# bpod_stepper_1_2_3.net
KiCad netlist of a schematic drawn in EAGLE
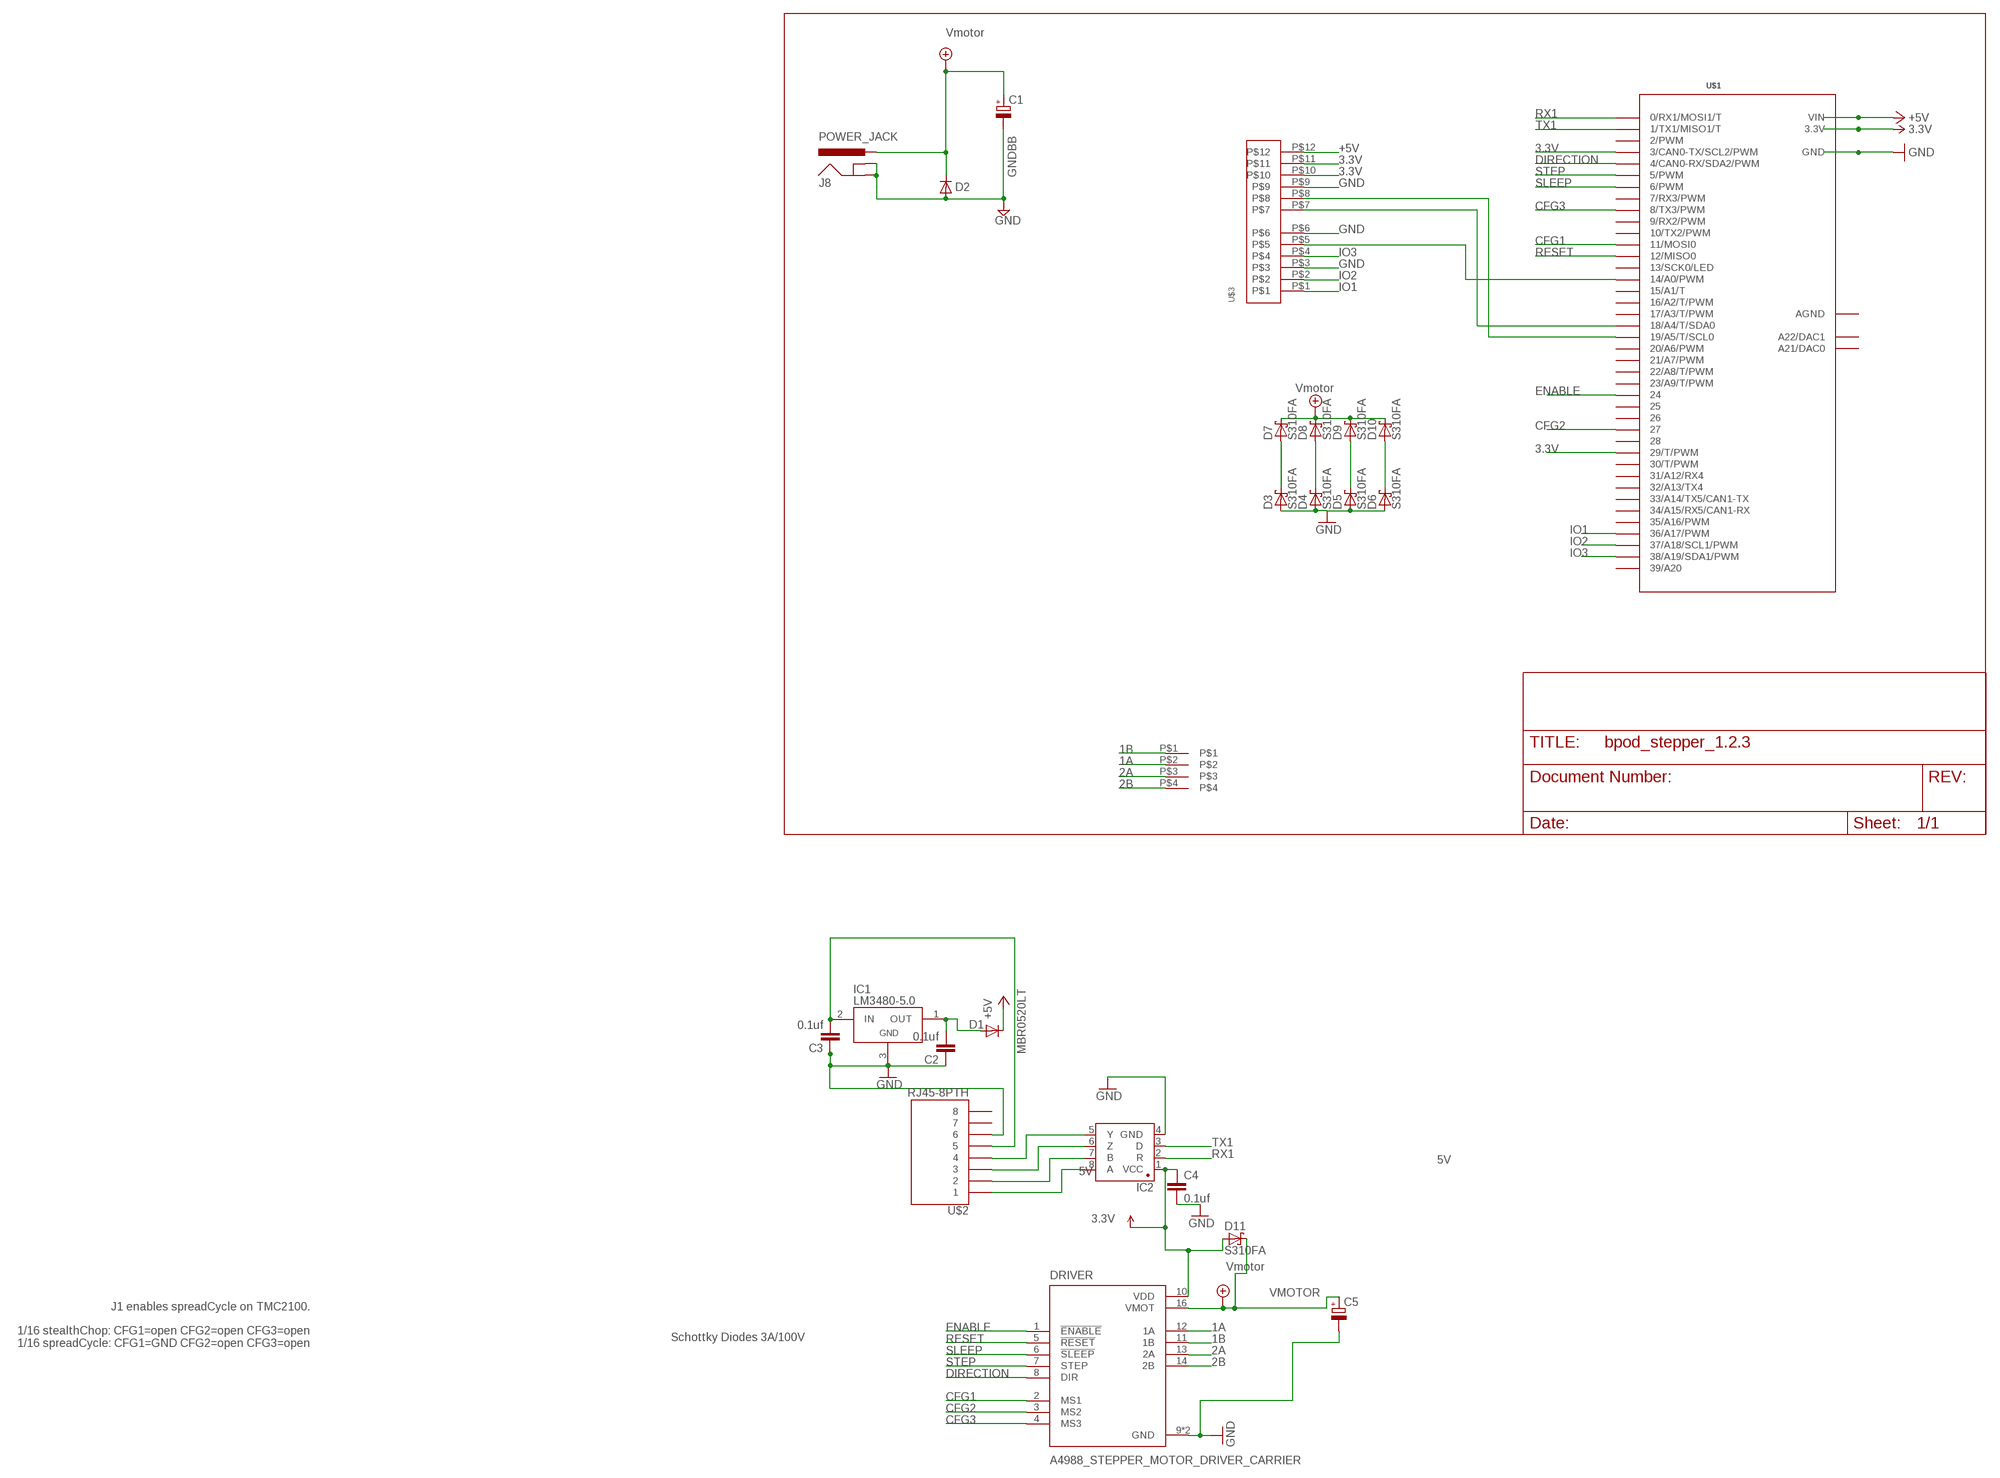
[diagram p0: schematic, sheet 1]

(export (version "E")
  (design (tool "Eeschema 10.0.6"))
  (components
    (comp (ref "C1")
      (value "CPOL-EUG")
      (footprint "eagle-import:PANASONIC_G")
      (libsource (lib "eagle-import") (part "CPOL-EUG"))
    )
    (comp (ref "C2")
      (value "0.1uf")
      (footprint "eagle-import:1206@1")
      (libsource (lib "eagle-import") (part "CAP1206"))
    )
    (comp (ref "C3")
      (value "0.1uf")
      (footprint "eagle-import:1206@1")
      (libsource (lib "eagle-import") (part "CAP1206"))
    )
    (comp (ref "C4")
      (value "0.1uf")
      (footprint "eagle-import:1206@1")
      (libsource (lib "eagle-import") (part "CAP1206"))
    )
    (comp (ref "C5")
      (value "CPOL-EUG")
      (footprint "eagle-import:PANASONIC_G")
      (libsource (lib "eagle-import") (part "CPOL-EUG"))
    )
    (comp (ref "D1")
      (value "MBR0520LT")
      (footprint "eagle-import:SOD123")
      (libsource (lib "eagle-import") (part "MBR0520LT"))
    )
    (comp (ref "D2")
      (value "DIODE-DO214AA")
      (footprint "eagle-import:DO214AA")
      (libsource (lib "eagle-import") (part "DIODE-DO214AA"))
    )
    (comp (ref "D3")
      (value "S310FA")
      (footprint "eagle-import:SOD123")
      (libsource (lib "eagle-import") (part "D_SCHOTTKY-SOD123"))
    )
    (comp (ref "D4")
      (value "S310FA")
      (footprint "eagle-import:SOD123")
      (libsource (lib "eagle-import") (part "D_SCHOTTKY-SOD123"))
    )
    (comp (ref "D5")
      (value "S310FA")
      (footprint "eagle-import:SOD123")
      (libsource (lib "eagle-import") (part "D_SCHOTTKY-SOD123"))
    )
    (comp (ref "D6")
      (value "S310FA")
      (footprint "eagle-import:SOD123")
      (libsource (lib "eagle-import") (part "D_SCHOTTKY-SOD123"))
    )
    (comp (ref "D7")
      (value "S310FA")
      (footprint "eagle-import:SOD123")
      (libsource (lib "eagle-import") (part "D_SCHOTTKY-SOD123"))
    )
    (comp (ref "D8")
      (value "S310FA")
      (footprint "eagle-import:SOD123")
      (libsource (lib "eagle-import") (part "D_SCHOTTKY-SOD123"))
    )
    (comp (ref "D9")
      (value "S310FA")
      (footprint "eagle-import:SOD123")
      (libsource (lib "eagle-import") (part "D_SCHOTTKY-SOD123"))
    )
    (comp (ref "D10")
      (value "S310FA")
      (footprint "eagle-import:SOD123")
      (libsource (lib "eagle-import") (part "D_SCHOTTKY-SOD123"))
    )
    (comp (ref "D11")
      (value "S310FA")
      (footprint "eagle-import:SOD123")
      (libsource (lib "eagle-import") (part "D_SCHOTTKY-SOD123"))
    )
    (comp (ref "DRIVER")
      (value "A4988_STEPPER_MOTOR_DRIVER_CARRIER")
      (footprint "eagle-import:MODULE_A4988_STEPPER_MOTOR_DRIVER_CARRIER")
      (fields (field (name "MF") "Pololu") (field (name "MP") "A4988 STEPPER MOTOR DRIVER CARRIER"))
      (libsource (lib "eagle-import") (part "A4988_STEPPER_MOTOR_DRIVER_CARRIER"))
    )
    (comp (ref "IC1")
      (value "LM3480-5.0")
      (footprint "eagle-import:SOT-23-3")
      (libsource (lib "eagle-import") (part "LM3480-5.0"))
    )
    (comp (ref "IC2")
      (value "SN65HVD31DR")
      (footprint "eagle-import:SO08")
      (libsource (lib "eagle-import") (part "SN65HVD31DR"))
    )
    (comp (ref "J8")
      (value "POWER_JACK")
      (footprint "eagle-import:POWER_JACK_PTH")
      (libsource (lib "eagle-import") (part "POWER_JACK"))
    )
    (comp (ref "U$1")
      (value "TEENSY_3.6_DIL")
      (footprint "eagle-import:TEENSY_3.6_DIL")
      (libsource (lib "eagle-import") (part "TEENSY_3.6_DIL"))
    )
    (comp (ref "U$2")
      (value "RJ45-8PTH")
      (footprint "eagle-import:RJ45-8")
      (libsource (lib "eagle-import") (part "RJ45-8PTH"))
    )
    (comp (ref "U$3")
      (value "12POS_MOLEX_SOCKET")
      (footprint "eagle-import:12POS_MOLEX_SOCKET")
      (libsource (lib "eagle-import") (part "12POS_MOLEX_SOCKET"))
    )
    (comp (ref "U$4")
      (value "MOLEX395221004")
      (footprint "eagle-import:MOLEX395221004")
      (libsource (lib "eagle-import") (part "MOLEX395221004"))
    )
  )
  (nets
    (net (code "1") (name "+5V") (class "Default")
      (node (ref "D1") (pin "C") (pinfunction "C_C") (pintype "passive"))
      (node (ref "U$1") (pin "VIN") (pinfunction "VIN_VIN") (pintype "power_in"))
      (node (ref "U$3") (pin "P$12") (pinfunction "P$12_P$12") (pintype "bidirectional"))
    )
    (net (code "2") (name "/1A") (class "Default")
      (node (ref "D4") (pin "C") (pinfunction "C_C") (pintype "passive"))
      (node (ref "D8") (pin "A") (pinfunction "A_A") (pintype "passive"))
      (node (ref "DRIVER") (pin "12") (pinfunction "1A_12") (pintype "output"))
      (node (ref "U$4") (pin "P$2") (pinfunction "P$2_P$2") (pintype "bidirectional"))
    )
    (net (code "3") (name "/1B") (class "Default")
      (node (ref "D3") (pin "C") (pinfunction "C_C") (pintype "passive"))
      (node (ref "D7") (pin "A") (pinfunction "A_A") (pintype "passive"))
      (node (ref "DRIVER") (pin "11") (pinfunction "1B_11") (pintype "output"))
      (node (ref "U$4") (pin "P$1") (pinfunction "P$1_P$1") (pintype "bidirectional"))
    )
    (net (code "4") (name "/2A") (class "Default")
      (node (ref "D5") (pin "C") (pinfunction "C_C") (pintype "passive"))
      (node (ref "D9") (pin "A") (pinfunction "A_A") (pintype "passive"))
      (node (ref "DRIVER") (pin "13") (pinfunction "2A_13") (pintype "output"))
      (node (ref "U$4") (pin "P$3") (pinfunction "P$3_P$3") (pintype "bidirectional"))
    )
    (net (code "5") (name "/2B") (class "Default")
      (node (ref "D10") (pin "A") (pinfunction "A_A") (pintype "passive"))
      (node (ref "D6") (pin "C") (pinfunction "C_C") (pintype "passive"))
      (node (ref "DRIVER") (pin "14") (pinfunction "2B_14") (pintype "output"))
      (node (ref "U$4") (pin "P$4") (pinfunction "P$4_P$4") (pintype "bidirectional"))
    )
    (net (code "6") (name "/AGND") (class "Default")
      (node (ref "U$1") (pin "AGND") (pinfunction "AGND_AGND") (pintype "power_in"))
    )
    (net (code "7") (name "/CFG1") (class "Default")
      (node (ref "DRIVER") (pin "2") (pinfunction "MS1_2") (pintype "input"))
      (node (ref "U$1") (pin "11") (pinfunction "11/MOSI0_11") (pintype "bidirectional"))
    )
    (net (code "8") (name "/CFG2") (class "Default")
      (node (ref "DRIVER") (pin "3") (pinfunction "MS2_3") (pintype "input"))
      (node (ref "U$1") (pin "27") (pinfunction "27_27") (pintype "bidirectional"))
    )
    (net (code "9") (name "/CFG3") (class "Default")
      (node (ref "DRIVER") (pin "4") (pinfunction "MS3_4") (pintype "input"))
      (node (ref "U$1") (pin "8") (pinfunction "8/TX3/PWM_8") (pintype "bidirectional"))
    )
    (net (code "10") (name "/DIRECTION") (class "Default")
      (node (ref "DRIVER") (pin "8") (pinfunction "DIR_8") (pintype "input"))
      (node (ref "U$1") (pin "4") (pinfunction "4/CAN0-RX/SDA2/PWM_4") (pintype "bidirectional"))
    )
    (net (code "11") (name "/ENABLE") (class "Default")
      (node (ref "DRIVER") (pin "1") (pinfunction "~{ENABLE}_1") (pintype "input"))
      (node (ref "U$1") (pin "24") (pinfunction "24_24") (pintype "bidirectional"))
    )
    (net (code "12") (name "/IO1") (class "Default")
      (node (ref "U$1") (pin "36/A17") (pinfunction "36/A17/PWM_36/A17") (pintype "bidirectional"))
      (node (ref "U$3") (pin "P$1") (pinfunction "P$1_P$1") (pintype "bidirectional"))
    )
    (net (code "13") (name "/IO2") (class "Default")
      (node (ref "U$1") (pin "37/A18") (pinfunction "37/A18/SCL1/PWM_37/A18") (pintype "bidirectional"))
      (node (ref "U$3") (pin "P$2") (pinfunction "P$2_P$2") (pintype "bidirectional"))
    )
    (net (code "14") (name "/IO3") (class "Default")
      (node (ref "U$1") (pin "38/A19") (pinfunction "38/A19/SDA1/PWM_38/A19") (pintype "bidirectional"))
      (node (ref "U$3") (pin "P$4") (pinfunction "P$4_P$4") (pintype "bidirectional"))
    )
    (net (code "15") (name "/RESET") (class "Default")
      (node (ref "DRIVER") (pin "5") (pinfunction "~{RESET}_5") (pintype "input"))
      (node (ref "U$1") (pin "12") (pinfunction "12/MISO0_12") (pintype "bidirectional"))
    )
    (net (code "16") (name "/RX1") (class "Default")
      (node (ref "IC2") (pin "2") (pinfunction "R_2") (pintype "bidirectional"))
      (node (ref "U$1") (pin "0") (pinfunction "0/RX1/MOSI1/T_0") (pintype "bidirectional"))
    )
    (net (code "17") (name "/SLEEP") (class "Default")
      (node (ref "DRIVER") (pin "6") (pinfunction "~{SLEEP}_6") (pintype "input"))
      (node (ref "U$1") (pin "6") (pinfunction "6/PWM_6") (pintype "bidirectional"))
    )
    (net (code "18") (name "/STEP") (class "Default")
      (node (ref "DRIVER") (pin "7") (pinfunction "STEP_7") (pintype "input"))
      (node (ref "U$1") (pin "5") (pinfunction "5/PWM_5") (pintype "bidirectional"))
    )
    (net (code "19") (name "/TX1") (class "Default")
      (node (ref "IC2") (pin "3") (pinfunction "D_3") (pintype "bidirectional"))
      (node (ref "U$1") (pin "1") (pinfunction "1/TX1/MISO1/T_1") (pintype "bidirectional"))
    )
    (net (code "20") (name "3.3V") (class "Default")
      (node (ref "C4") (pin "1") (pinfunction "1_1") (pintype "passive"))
      (node (ref "D11") (pin "A") (pinfunction "A_A") (pintype "passive"))
      (node (ref "DRIVER") (pin "10") (pinfunction "VDD_10") (pintype "power_in"))
      (node (ref "IC2") (pin "1") (pinfunction "VCC_1") (pintype "bidirectional"))
      (node (ref "U$1") (pin "29") (pinfunction "29/T/PWM_29") (pintype "bidirectional"))
      (node (ref "U$1") (pin "3") (pinfunction "3/CAN0-TX/SCL2/PWM_3") (pintype "bidirectional"))
      (node (ref "U$1") (pin "3.3V") (pinfunction "3.3V_3.3V") (pintype "power_in"))
      (node (ref "U$1") (pin "3.3V3") (pinfunction "3.3V_3.3V3") (pintype "power_in"))
      (node (ref "U$3") (pin "P$10") (pinfunction "P$10_P$10") (pintype "bidirectional"))
      (node (ref "U$3") (pin "P$11") (pinfunction "P$11_P$11") (pintype "bidirectional"))
    )
    (net (code "21") (name "GND") (class "Default")
      (node (ref "C1") (pin "-") (pinfunction "-_-") (pintype "passive"))
      (node (ref "C2") (pin "1") (pinfunction "1_1") (pintype "passive"))
      (node (ref "C3") (pin "1") (pinfunction "1_1") (pintype "passive"))
      (node (ref "C4") (pin "2") (pinfunction "2_2") (pintype "passive"))
      (node (ref "C5") (pin "-") (pinfunction "-_-") (pintype "passive"))
      (node (ref "D2") (pin "A") (pinfunction "A_A") (pintype "passive"))
      (node (ref "D3") (pin "A") (pinfunction "A_A") (pintype "passive"))
      (node (ref "D4") (pin "A") (pinfunction "A_A") (pintype "passive"))
      (node (ref "D5") (pin "A") (pinfunction "A_A") (pintype "passive"))
      (node (ref "D6") (pin "A") (pinfunction "A_A") (pintype "passive"))
      (node (ref "DRIVER") (pin "15") (pinfunction "GND_15") (pintype "power_in"))
      (node (ref "DRIVER") (pin "9") (pinfunction "GND_9") (pintype "power_in"))
      (node (ref "IC1") (pin "3") (pinfunction "GND_3") (pintype "power_in"))
      (node (ref "IC2") (pin "4") (pinfunction "GND_4") (pintype "bidirectional"))
      (node (ref "J8") (pin "GND") (pinfunction "GND_GND") (pintype "bidirectional"))
      (node (ref "J8") (pin "GNDBREAK") (pinfunction "GNDBREAK_GNDBREAK") (pintype "bidirectional"))
      (node (ref "U$1") (pin "GND") (pinfunction "GND_GND") (pintype "power_in"))
      (node (ref "U$1") (pin "GND1") (pinfunction "GND_GND1") (pintype "power_in"))
      (node (ref "U$2") (pin "6") (pinfunction "6_6") (pintype "bidirectional"))
      (node (ref "U$3") (pin "P$3") (pinfunction "P$3_P$3") (pintype "bidirectional"))
      (node (ref "U$3") (pin "P$6") (pinfunction "P$6_P$6") (pintype "bidirectional"))
      (node (ref "U$3") (pin "P$9") (pinfunction "P$9_P$9") (pintype "bidirectional"))
    )
    (net (code "22") (name "Net-(IC1-IN)") (class "Default")
      (node (ref "C3") (pin "2") (pinfunction "2_2") (pintype "passive"))
      (node (ref "IC1") (pin "2") (pinfunction "IN_2") (pintype "power_in"))
      (node (ref "U$2") (pin "5") (pinfunction "5_5") (pintype "bidirectional"))
    )
    (net (code "23") (name "Net-(IC1-OUT)") (class "Default")
      (node (ref "C2") (pin "2") (pinfunction "2_2") (pintype "passive"))
      (node (ref "D1") (pin "A") (pinfunction "A_A") (pintype "passive"))
      (node (ref "IC1") (pin "1") (pinfunction "OUT_1") (pintype "power_in"))
    )
    (net (code "24") (name "Net-(IC2-A)") (class "Default")
      (node (ref "IC2") (pin "8") (pinfunction "A_8") (pintype "bidirectional"))
      (node (ref "U$2") (pin "1") (pinfunction "1_1") (pintype "bidirectional"))
    )
    (net (code "25") (name "Net-(IC2-B)") (class "Default")
      (node (ref "IC2") (pin "7") (pinfunction "B_7") (pintype "bidirectional"))
      (node (ref "U$2") (pin "2") (pinfunction "2_2") (pintype "bidirectional"))
    )
    (net (code "26") (name "Net-(IC2-Y)") (class "Default")
      (node (ref "IC2") (pin "5") (pinfunction "Y_5") (pintype "bidirectional"))
      (node (ref "U$2") (pin "4") (pinfunction "4_4") (pintype "bidirectional"))
    )
    (net (code "27") (name "Net-(IC2-Z)") (class "Default")
      (node (ref "IC2") (pin "6") (pinfunction "Z_6") (pintype "bidirectional"))
      (node (ref "U$2") (pin "3") (pinfunction "3_3") (pintype "bidirectional"))
    )
    (net (code "28") (name "Net-(U$1-14{slash}A0{slash}PWM)") (class "Default")
      (node (ref "U$1") (pin "14/A0") (pinfunction "14/A0/PWM_14/A0") (pintype "bidirectional"))
      (node (ref "U$3") (pin "P$5") (pinfunction "P$5_P$5") (pintype "bidirectional"))
    )
    (net (code "29") (name "Net-(U$1-18{slash}A4{slash}T{slash}SDA0)") (class "Default")
      (node (ref "U$1") (pin "18/A4") (pinfunction "18/A4/T/SDA0_18/A4") (pintype "bidirectional"))
      (node (ref "U$3") (pin "P$7") (pinfunction "P$7_P$7") (pintype "bidirectional"))
    )
    (net (code "30") (name "Net-(U$1-19{slash}A5{slash}T{slash}SCL0)") (class "Default")
      (node (ref "U$1") (pin "19/A5") (pinfunction "19/A5/T/SCL0_19/A5") (pintype "bidirectional"))
      (node (ref "U$3") (pin "P$8") (pinfunction "P$8_P$8") (pintype "bidirectional"))
    )
    (net (code "31") (name "Vmotor") (class "Default")
      (node (ref "C1") (pin "+") (pinfunction "+_+") (pintype "passive"))
      (node (ref "C5") (pin "+") (pinfunction "+_+") (pintype "passive"))
      (node (ref "D10") (pin "C") (pinfunction "C_C") (pintype "passive"))
      (node (ref "D11") (pin "C") (pinfunction "C_C") (pintype "passive"))
      (node (ref "D2") (pin "C") (pinfunction "C_C") (pintype "passive"))
      (node (ref "D7") (pin "C") (pinfunction "C_C") (pintype "passive"))
      (node (ref "D8") (pin "C") (pinfunction "C_C") (pintype "passive"))
      (node (ref "D9") (pin "C") (pinfunction "C_C") (pintype "passive"))
      (node (ref "DRIVER") (pin "16") (pinfunction "VMOT_16") (pintype "power_in"))
      (node (ref "J8") (pin "PWR") (pinfunction "PWR_PWR") (pintype "bidirectional"))
    )
    (net (code "32") (name "unconnected-(U$1-2{slash}PWM-Pad2)") (class "Default")
      (node (ref "U$1") (pin "2") (pinfunction "2/PWM_2") (pintype "bidirectional"))
    )
    (net (code "33") (name "unconnected-(U$1-7{slash}RX3{slash}PWM-Pad7)") (class "Default")
      (node (ref "U$1") (pin "7") (pinfunction "7/RX3/PWM_7") (pintype "bidirectional"))
    )
    (net (code "34") (name "unconnected-(U$1-9{slash}RX2{slash}PWM-Pad9)") (class "Default")
      (node (ref "U$1") (pin "9") (pinfunction "9/RX2/PWM_9") (pintype "bidirectional"))
    )
    (net (code "35") (name "unconnected-(U$1-10{slash}TX2{slash}PWM-Pad10)") (class "Default")
      (node (ref "U$1") (pin "10") (pinfunction "10/TX2/PWM_10") (pintype "bidirectional"))
    )
    (net (code "36") (name "unconnected-(U$1-13{slash}SCK0{slash}LED-Pad13)") (class "Default")
      (node (ref "U$1") (pin "13") (pinfunction "13/SCK0/LED_13") (pintype "bidirectional"))
    )
    (net (code "37") (name "unconnected-(U$1-15{slash}A1{slash}T-Pad15{slash}A1)") (class "Default")
      (node (ref "U$1") (pin "15/A1") (pinfunction "15/A1/T_15/A1") (pintype "bidirectional"))
    )
    (net (code "38") (name "unconnected-(U$1-16{slash}A2{slash}T{slash}PWM-Pad16{slash}A2)") (class "Default")
      (node (ref "U$1") (pin "16/A2") (pinfunction "16/A2/T/PWM_16/A2") (pintype "bidirectional"))
    )
    (net (code "39") (name "unconnected-(U$1-17{slash}A3{slash}T{slash}PWM-Pad17{slash}A3)") (class "Default")
      (node (ref "U$1") (pin "17/A3") (pinfunction "17/A3/T/PWM_17/A3") (pintype "bidirectional"))
    )
    (net (code "40") (name "unconnected-(U$1-20{slash}A6{slash}PWM-Pad20{slash}A6)") (class "Default")
      (node (ref "U$1") (pin "20/A6") (pinfunction "20/A6/PWM_20/A6") (pintype "bidirectional"))
    )
    (net (code "41") (name "unconnected-(U$1-21{slash}A7{slash}PWM-Pad21{slash}A7)") (class "Default")
      (node (ref "U$1") (pin "21/A7") (pinfunction "21/A7/PWM_21/A7") (pintype "bidirectional"))
    )
    (net (code "42") (name "unconnected-(U$1-22{slash}A8{slash}T{slash}PWM-Pad22{slash}A8)") (class "Default")
      (node (ref "U$1") (pin "22/A8") (pinfunction "22/A8/T/PWM_22/A8") (pintype "bidirectional"))
    )
    (net (code "43") (name "unconnected-(U$1-23{slash}A9{slash}T{slash}PWM-Pad23{slash}A9)") (class "Default")
      (node (ref "U$1") (pin "23/A9") (pinfunction "23/A9/T/PWM_23/A9") (pintype "bidirectional"))
    )
    (net (code "44") (name "unconnected-(U$1-30{slash}T{slash}PWM-Pad30)") (class "Default")
      (node (ref "U$1") (pin "30") (pinfunction "30/T/PWM_30") (pintype "bidirectional"))
    )
    (net (code "45") (name "unconnected-(U$1-31{slash}A12{slash}RX4-Pad31{slash}A12)") (class "Default")
      (node (ref "U$1") (pin "31/A12") (pinfunction "31/A12/RX4_31/A12") (pintype "bidirectional"))
    )
    (net (code "46") (name "unconnected-(U$1-32{slash}A13{slash}TX4-Pad32{slash}A13)") (class "Default")
      (node (ref "U$1") (pin "32/A13") (pinfunction "32/A13/TX4_32/A13") (pintype "bidirectional"))
    )
    (net (code "47") (name "unconnected-(U$1-33{slash}A14{slash}TX5{slash}CAN1-TX-Pad33{slash}A14)") (class "Default")
      (node (ref "U$1") (pin "33/A14") (pinfunction "33/A14/TX5/CAN1-TX_33/A14") (pintype "bidirectional"))
    )
    (net (code "48") (name "unconnected-(U$1-34{slash}A15{slash}RX5{slash}CAN1-RX-Pad34{slash}A15)") (class "Default")
      (node (ref "U$1") (pin "34/A15") (pinfunction "34/A15/RX5/CAN1-RX_34/A15") (pintype "bidirectional"))
    )
    (net (code "49") (name "unconnected-(U$1-35{slash}A16{slash}PWM-Pad35{slash}A16)") (class "Default")
      (node (ref "U$1") (pin "35/A16") (pinfunction "35/A16/PWM_35/A16") (pintype "bidirectional"))
    )
    (net (code "50") (name "unconnected-(U$1-A21{slash}DAC0-PadA21)") (class "Default")
      (node (ref "U$1") (pin "A21") (pinfunction "A21/DAC0_A21") (pintype "bidirectional"))
    )
    (net (code "51") (name "unconnected-(U$1-A22{slash}DAC1-PadA22)") (class "Default")
      (node (ref "U$1") (pin "A22") (pinfunction "A22/DAC1_A22") (pintype "bidirectional"))
    )
    (net (code "52") (name "unconnected-(U$1-Pad25)") (class "Default")
      (node (ref "U$1") (pin "25") (pinfunction "25_25") (pintype "bidirectional"))
    )
    (net (code "53") (name "unconnected-(U$1-Pad26)") (class "Default")
      (node (ref "U$1") (pin "26") (pinfunction "26_26") (pintype "bidirectional"))
    )
    (net (code "54") (name "unconnected-(U$1-Pad28)") (class "Default")
      (node (ref "U$1") (pin "28") (pinfunction "28_28") (pintype "bidirectional"))
    )
    (net (code "55") (name "unconnected-(U$1-Pad39{slash}A20)") (class "Default")
      (node (ref "U$1") (pin "39/A20") (pinfunction "39/A20_39/A20") (pintype "bidirectional"))
    )
    (net (code "56") (name "unconnected-(U$2-Pad7)") (class "Default")
      (node (ref "U$2") (pin "7") (pinfunction "7_7") (pintype "bidirectional"))
    )
    (net (code "57") (name "unconnected-(U$2-Pad8)") (class "Default")
      (node (ref "U$2") (pin "8") (pinfunction "8_8") (pintype "bidirectional"))
    )
  )
)
